# Sheet1.net
KiCad netlist of a schematic drawn in Altium Designer
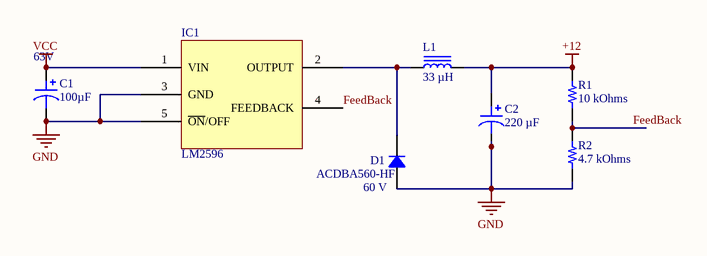
[diagram p0: Sheet1.SchDoc]

(export (version "E")
  (design (tool "Eeschema 10.0.6"))
  (components
    (comp (ref "C1")
      (value "100µF")
      (footprint "CAP TH ALUM ELEC D10.00mm S5.00mm H10.50mm")
      (description "CAP ALUM 100UF 20% 63V RADIAL")
      (fields
        (field (name "PART NUMBER") "URS1J101MPD1TD")
        (field (name "MANUFACTURER") "Nichicon")
        (field (name "VOLTAGE - RATED") "63V")
      )
      (libsource (lib "Celestial Altium Library - altium_library") (part "Polarised Capacitor"))
    )
    (comp (ref "C2")
      (value "220 µF")
      (footprint "CAP TH ALPOLY D8.00mm S3.50mm H13.50mm")
      (description "CAP ALUM POLY 220UF 20% 35V T/H")
      (fields (field (name "PART NUMBER") "227AVG035MFBJ") (field (name "MANUFACTURER") "Illinois Capacitor"))
      (libsource (lib "Celestial Altium Library - altium_library") (part "Polarised Capacitor"))
    )
    (comp (ref "D1")
      (value "ACDBA560-HF")
      (footprint "DO214AC SMA")
      (description "DIODE SCHOTTKY 60V 5A DO214AC")
      (fields
        (field (name "MANUFACTURER") "Comchip Technology")
        (field (name "VOLTAGE - DC REVERSE (VR) (MAX)") "60 V")
      )
      (libsource (lib "Celestial Altium Library - altium_library") (part "Diode"))
    )
    (comp (ref "IC1")
      (value "LM2596")
      (footprint "PcbLib1:D2PAK")
      (libsource (lib "Schlib1") (part "LM2596"))
    )
    (comp (ref "L1")
      (value "33 µH")
      (footprint "BOURNS SRR1280")
      (description "FIXED IND 33UH 3.5A 57 MOHM SMD")
      (fields (field (name "PART NUMBER") "SRR1280-330M") (field (name "MANUFACTURER") "Bourns Inc."))
      (libsource (lib "Celestial Altium Library - altium_library") (part "Inductor"))
    )
    (comp (ref "R1")
      (value "10 kOhms")
      (footprint "RES 0805_2012")
      (description "RES 10K OHM 1% 1/3W 0805")
      (fields
        (field (name "PART NUMBER") "CRGP0805F10K")
        (field (name "MANUFACTURER") "TE Connectivity Passive Product")
      )
      (libsource (lib "Celestial Altium Library - altium_library") (part "Resistor"))
    )
    (comp (ref "R2")
      (value "4.7 kOhms")
      (footprint "RES 0805_2012")
      (description "RES 4.7K OHM 1% 1/3W 0805")
      (fields
        (field (name "PART NUMBER") "CRGP0805F4K7")
        (field (name "MANUFACTURER") "TE Connectivity Passive Product")
      )
      (libsource (lib "Celestial Altium Library - altium_library") (part "Resistor"))
    )
  )
  (nets
    (net (code "1") (name "+12") (class "Default")
      (node (ref "C2") (pin "1") (pinfunction "1_1") (pintype "passive"))
      (node (ref "L1") (pin "2") (pinfunction "2_2") (pintype "passive"))
      (node (ref "R1") (pin "2") (pinfunction "2_2") (pintype "passive"))
    )
    (net (code "2") (name "/FeedBack") (class "Default")
      (node (ref "IC1") (pin "4") (pinfunction "FEEDBACK_4") (pintype "passive"))
      (node (ref "R1") (pin "1") (pinfunction "1_1") (pintype "passive"))
      (node (ref "R2") (pin "2") (pinfunction "2_2") (pintype "passive"))
    )
    (net (code "3") (name "GND") (class "Default")
      (node (ref "C1") (pin "2") (pinfunction "2_2") (pintype "passive"))
      (node (ref "C2") (pin "2") (pinfunction "2_2") (pintype "passive"))
      (node (ref "D1") (pin "1") (pinfunction "1_1") (pintype "passive"))
      (node (ref "IC1") (pin "3") (pinfunction "GND_3") (pintype "passive"))
      (node (ref "IC1") (pin "5") (pinfunction "~{ON}/OFF_5") (pintype "passive"))
      (node (ref "R2") (pin "1") (pinfunction "1_1") (pintype "passive"))
    )
    (net (code "4") (name "Net-(IC1-OUTPUT)") (class "Default")
      (node (ref "D1") (pin "2") (pinfunction "2_2") (pintype "passive"))
      (node (ref "IC1") (pin "2") (pinfunction "OUTPUT_2") (pintype "passive"))
      (node (ref "L1") (pin "1") (pinfunction "1_1") (pintype "passive"))
    )
    (net (code "5") (name "VCC") (class "Default")
      (node (ref "C1") (pin "1") (pinfunction "1_1") (pintype "passive"))
      (node (ref "IC1") (pin "1") (pinfunction "VIN_1") (pintype "passive"))
    )
  )
)
